# RCM-Comm_v4.net
KiCad netlist of a schematic drawn in EAGLE
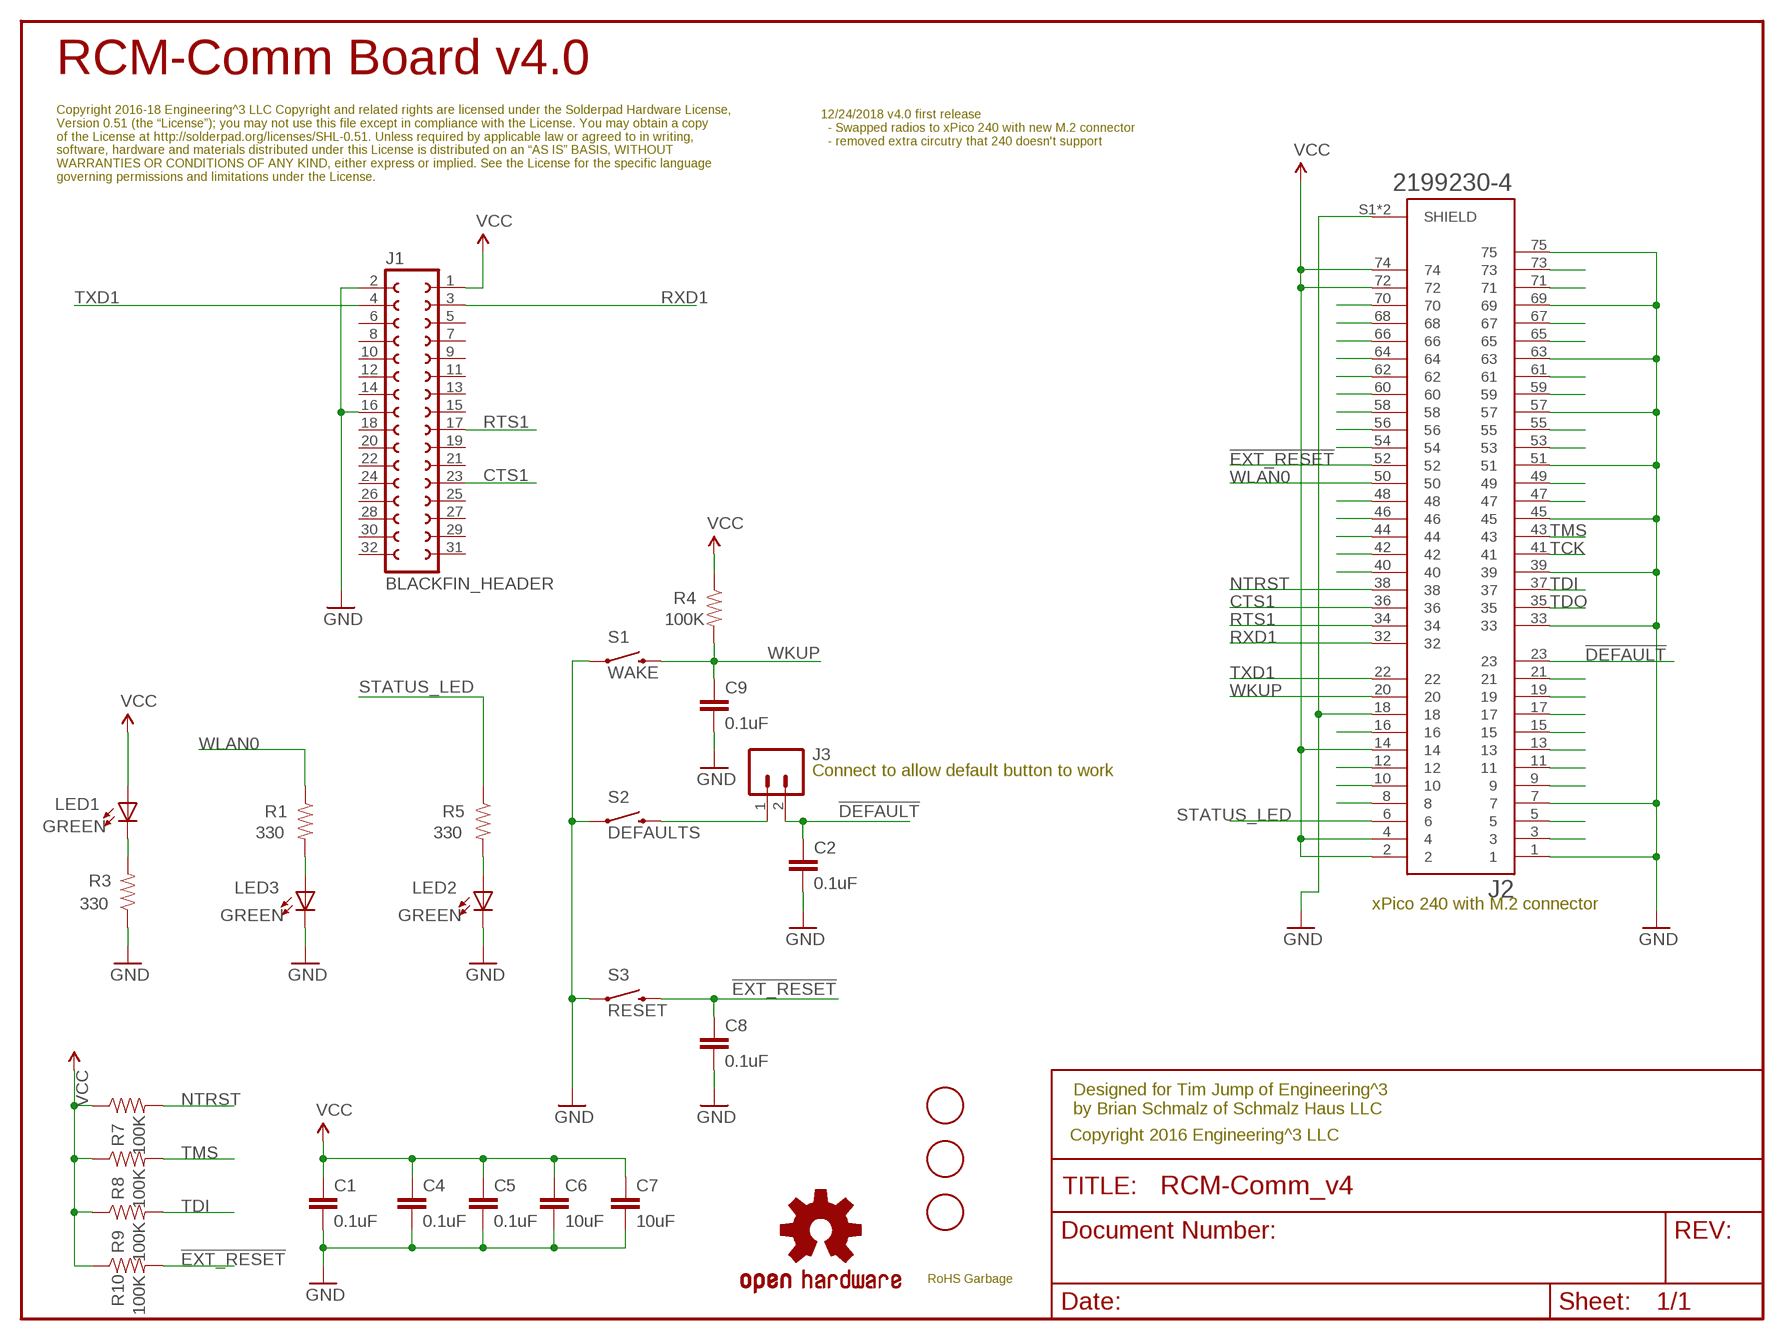
[diagram p0: schematic, sheet 1]

(export (version "E")
  (design (tool "Eeschema 10.0.6"))
  (components
    (comp (ref "C1")
      (value "0.1uF")
      (footprint "eagle-import:0603-CAP")
      (libsource (lib "eagle-import") (part "0.1UF-25V(+80/-20%)(0603)"))
    )
    (comp (ref "C2")
      (value "0.1uF")
      (footprint "eagle-import:0603-CAP")
      (libsource (lib "eagle-import") (part "0.1UF-25V(+80/-20%)(0603)"))
    )
    (comp (ref "C4")
      (value "0.1uF")
      (footprint "eagle-import:0603-CAP")
      (libsource (lib "eagle-import") (part "0.1UF-25V(+80/-20%)(0603)"))
    )
    (comp (ref "C5")
      (value "0.1uF")
      (footprint "eagle-import:0603-CAP")
      (libsource (lib "eagle-import") (part "0.1UF-25V(+80/-20%)(0603)"))
    )
    (comp (ref "C6")
      (value "10uF")
      (footprint "eagle-import:0603-CAP")
      (libsource (lib "eagle-import") (part "10UF-6.3V-20%(0603)"))
    )
    (comp (ref "C7")
      (value "10uF")
      (footprint "eagle-import:0603-CAP")
      (libsource (lib "eagle-import") (part "10UF-6.3V-20%(0603)"))
    )
    (comp (ref "C8")
      (value "0.1uF")
      (footprint "eagle-import:0603-CAP")
      (libsource (lib "eagle-import") (part "0.1UF-25V(+80/-20%)(0603)"))
    )
    (comp (ref "C9")
      (value "0.1uF")
      (footprint "eagle-import:0603-CAP")
      (libsource (lib "eagle-import") (part "0.1UF-25V(+80/-20%)(0603)"))
    )
    (comp (ref "FID1")
      (value "FIDUCIAL")
      (footprint "eagle-import:FIDUCIAL_1MM")
      (libsource (lib "eagle-import") (part "FIDUCIAL"))
    )
    (comp (ref "FID2")
      (value "FIDUCIAL")
      (footprint "eagle-import:FIDUCIAL_1MM")
      (libsource (lib "eagle-import") (part "FIDUCIAL"))
    )
    (comp (ref "FID3")
      (value "FIDUCIAL")
      (footprint "eagle-import:FIDUCIAL_1MM")
      (libsource (lib "eagle-import") (part "FIDUCIAL"))
    )
    (comp (ref "J1")
      (value "BLACKFIN_HEADER")
      (footprint "eagle-import:2X16")
      (libsource (lib "eagle-import") (part "BLACKFIN_HEADER"))
    )
    (comp (ref "J2")
      (value "2199230-4")
      (footprint "eagle-import:TE_2199230-4")
      (fields (field (name "DIGI-KEY_PART_NUMBER") "A115904CT-ND") (field (name "MF") "TE Connectivity"))
      (libsource (lib "eagle-import") (part "2199230-4"))
    )
    (comp (ref "J3")
      (value "CONN_02")
      (footprint "eagle-import:1X02")
      (libsource (lib "eagle-import") (part "CONN_02"))
    )
    (comp (ref "LED1")
      (value "GREEN")
      (footprint "eagle-import:LED-0603")
      (libsource (lib "eagle-import") (part "LED0603"))
    )
    (comp (ref "LED2")
      (value "GREEN")
      (footprint "eagle-import:LED-0603")
      (libsource (lib "eagle-import") (part "LED0603"))
    )
    (comp (ref "LED3")
      (value "GREEN")
      (footprint "eagle-import:LED-0603")
      (libsource (lib "eagle-import") (part "LED0603"))
    )
    (comp (ref "LOGO1")
      (value "OSHW-LOGOM")
      (footprint "eagle-import:OSHW-LOGO-M")
      (libsource (lib "eagle-import") (part "OSHW-LOGOM"))
    )
    (comp (ref "R1")
      (value "330")
      (footprint "eagle-import:0603-RES")
      (libsource (lib "eagle-import") (part "RESISTOR0603-RES"))
    )
    (comp (ref "R3")
      (value "330")
      (footprint "eagle-import:0603-RES")
      (libsource (lib "eagle-import") (part "RESISTOR0603-RES"))
    )
    (comp (ref "R4")
      (value "100K")
      (footprint "eagle-import:0603-RES")
      (libsource (lib "eagle-import") (part "RESISTOR0603-RES"))
    )
    (comp (ref "R5")
      (value "330")
      (footprint "eagle-import:0603-RES")
      (libsource (lib "eagle-import") (part "RESISTOR0603-RES"))
    )
    (comp (ref "R7")
      (value "100K")
      (footprint "eagle-import:0603-RES")
      (libsource (lib "eagle-import") (part "RESISTOR0603-RES"))
    )
    (comp (ref "R8")
      (value "100K")
      (footprint "eagle-import:0603-RES")
      (libsource (lib "eagle-import") (part "RESISTOR0603-RES"))
    )
    (comp (ref "R9")
      (value "100K")
      (footprint "eagle-import:0603-RES")
      (libsource (lib "eagle-import") (part "RESISTOR0603-RES"))
    )
    (comp (ref "R10")
      (value "100K")
      (footprint "eagle-import:0603-RES")
      (libsource (lib "eagle-import") (part "RESISTOR0603-RES"))
    )
    (comp (ref "S1")
      (value "WAKE")
      (footprint "eagle-import:TACTILE-SWITCH-SMD")
      (libsource (lib "eagle-import") (part "SWITCH-MOMENTARY-2SMD"))
    )
    (comp (ref "S2")
      (value "DEFAULTS")
      (footprint "eagle-import:TACTILE-SWITCH-SMD")
      (libsource (lib "eagle-import") (part "SWITCH-MOMENTARY-2SMD"))
    )
    (comp (ref "S3")
      (value "RESET")
      (footprint "eagle-import:TACTILE-SWITCH-SMD")
      (libsource (lib "eagle-import") (part "SWITCH-MOMENTARY-2SMD"))
    )
    (comp (ref "U$3")
      (value "ROHS_GARBAGE")
      (footprint "eagle-import:ROHS_GARBAGE_5MM")
      (libsource (lib "eagle-import") (part "ROHS_GARBAGE"))
    )
  )
  (nets
    (net (code "1") (name "/CTS1") (class "Default")
      (node (ref "J1") (pin "23") (pinfunction "GP6_23") (pintype "passive"))
      (node (ref "J2") (pin "36") (pinfunction "36_36") (pintype "passive"))
    )
    (net (code "2") (name "/NTRST") (class "Default")
      (node (ref "J2") (pin "38") (pinfunction "38_38") (pintype "passive"))
      (node (ref "R7") (pin "2") (pinfunction "2_2") (pintype "passive"))
    )
    (net (code "3") (name "/RTS1") (class "Default")
      (node (ref "J1") (pin "17") (pinfunction "GP0_17") (pintype "passive"))
      (node (ref "J2") (pin "34") (pinfunction "34_34") (pintype "passive"))
    )
    (net (code "4") (name "/RXD1") (class "Default")
      (node (ref "J1") (pin "3") (pinfunction "TX0_3") (pintype "passive"))
      (node (ref "J2") (pin "32") (pinfunction "32_32") (pintype "passive"))
    )
    (net (code "5") (name "/STATUS_LED") (class "Default")
      (node (ref "J2") (pin "6") (pinfunction "6_6") (pintype "passive"))
      (node (ref "R5") (pin "1") (pinfunction "1_1") (pintype "passive"))
    )
    (net (code "6") (name "/TCK") (class "Default")
      (node (ref "J2") (pin "41") (pinfunction "41_41") (pintype "passive"))
    )
    (net (code "7") (name "/TDI") (class "Default")
      (node (ref "J2") (pin "37") (pinfunction "37_37") (pintype "passive"))
      (node (ref "R9") (pin "2") (pinfunction "2_2") (pintype "passive"))
    )
    (net (code "8") (name "/TDO") (class "Default")
      (node (ref "J2") (pin "35") (pinfunction "35_35") (pintype "passive"))
    )
    (net (code "9") (name "/TMS") (class "Default")
      (node (ref "J2") (pin "43") (pinfunction "43_43") (pintype "passive"))
      (node (ref "R8") (pin "2") (pinfunction "2_2") (pintype "passive"))
    )
    (net (code "10") (name "/TXD1") (class "Default")
      (node (ref "J1") (pin "4") (pinfunction "RX0_4") (pintype "passive"))
      (node (ref "J2") (pin "22") (pinfunction "22_22") (pintype "passive"))
    )
    (net (code "11") (name "/WKUP") (class "Default")
      (node (ref "C9") (pin "1") (pinfunction "1_1") (pintype "passive"))
      (node (ref "J2") (pin "20") (pinfunction "20_20") (pintype "passive"))
      (node (ref "R4") (pin "2") (pinfunction "2_2") (pintype "passive"))
      (node (ref "S1") (pin "3") (pinfunction "2_3") (pintype "passive"))
    )
    (net (code "12") (name "/WLAN0") (class "Default")
      (node (ref "J2") (pin "50") (pinfunction "50_50") (pintype "passive"))
      (node (ref "R1") (pin "1") (pinfunction "1_1") (pintype "passive"))
    )
    (net (code "13") (name "/~{DEFAULT}") (class "Default")
      (node (ref "C2") (pin "1") (pinfunction "1_1") (pintype "passive"))
      (node (ref "J2") (pin "23") (pinfunction "23_23") (pintype "passive"))
      (node (ref "J3") (pin "2") (pinfunction "2_2") (pintype "passive"))
    )
    (net (code "14") (name "/~{EXT_RESET}") (class "Default")
      (node (ref "C8") (pin "1") (pinfunction "1_1") (pintype "passive"))
      (node (ref "J2") (pin "52") (pinfunction "52_52") (pintype "passive"))
      (node (ref "R10") (pin "2") (pinfunction "2_2") (pintype "passive"))
      (node (ref "S3") (pin "3") (pinfunction "2_3") (pintype "passive"))
    )
    (net (code "15") (name "GND") (class "Default")
      (node (ref "C1") (pin "2") (pinfunction "2_2") (pintype "passive"))
      (node (ref "C2") (pin "2") (pinfunction "2_2") (pintype "passive"))
      (node (ref "C4") (pin "2") (pinfunction "2_2") (pintype "passive"))
      (node (ref "C5") (pin "2") (pinfunction "2_2") (pintype "passive"))
      (node (ref "C6") (pin "2") (pinfunction "2_2") (pintype "passive"))
      (node (ref "C7") (pin "2") (pinfunction "2_2") (pintype "passive"))
      (node (ref "C8") (pin "2") (pinfunction "2_2") (pintype "passive"))
      (node (ref "C9") (pin "2") (pinfunction "2_2") (pintype "passive"))
      (node (ref "J1") (pin "16") (pinfunction "GND16_16") (pintype "passive"))
      (node (ref "J1") (pin "2") (pinfunction "GND_2") (pintype "passive"))
      (node (ref "J2") (pin "1") (pinfunction "1_1") (pintype "passive"))
      (node (ref "J2") (pin "18") (pinfunction "18_18") (pintype "passive"))
      (node (ref "J2") (pin "33") (pinfunction "33_33") (pintype "passive"))
      (node (ref "J2") (pin "39") (pinfunction "39_39") (pintype "passive"))
      (node (ref "J2") (pin "45") (pinfunction "45_45") (pintype "passive"))
      (node (ref "J2") (pin "51") (pinfunction "51_51") (pintype "passive"))
      (node (ref "J2") (pin "57") (pinfunction "57_57") (pintype "passive"))
      (node (ref "J2") (pin "63") (pinfunction "63_63") (pintype "passive"))
      (node (ref "J2") (pin "69") (pinfunction "69_69") (pintype "passive"))
      (node (ref "J2") (pin "7") (pinfunction "7_7") (pintype "passive"))
      (node (ref "J2") (pin "75") (pinfunction "75_75") (pintype "passive"))
      (node (ref "J2") (pin "S1") (pinfunction "SHIELD_S1") (pintype "passive"))
      (node (ref "J2") (pin "S2") (pinfunction "SHIELD_S2") (pintype "passive"))
      (node (ref "LED2") (pin "C") (pinfunction "C_C") (pintype "passive"))
      (node (ref "LED3") (pin "C") (pinfunction "C_C") (pintype "passive"))
      (node (ref "R3") (pin "1") (pinfunction "1_1") (pintype "passive"))
      (node (ref "S1") (pin "1") (pinfunction "1_1") (pintype "passive"))
      (node (ref "S2") (pin "1") (pinfunction "1_1") (pintype "passive"))
      (node (ref "S3") (pin "1") (pinfunction "1_1") (pintype "passive"))
    )
    (net (code "16") (name "Net-(LED1-PadC)") (class "Default")
      (node (ref "LED1") (pin "C") (pinfunction "C_C") (pintype "passive"))
      (node (ref "R3") (pin "2") (pinfunction "2_2") (pintype "passive"))
    )
    (net (code "17") (name "Net-(LED2-PadA)") (class "Default")
      (node (ref "LED2") (pin "A") (pinfunction "A_A") (pintype "passive"))
      (node (ref "R5") (pin "2") (pinfunction "2_2") (pintype "passive"))
    )
    (net (code "18") (name "Net-(LED3-PadA)") (class "Default")
      (node (ref "LED3") (pin "A") (pinfunction "A_A") (pintype "passive"))
      (node (ref "R1") (pin "2") (pinfunction "2_2") (pintype "passive"))
    )
    (net (code "19") (name "Net-(S2-2)") (class "Default")
      (node (ref "J3") (pin "1") (pinfunction "1_1") (pintype "passive"))
      (node (ref "S2") (pin "3") (pinfunction "2_3") (pintype "passive"))
    )
    (net (code "20") (name "VCC") (class "Default")
      (node (ref "C1") (pin "1") (pinfunction "1_1") (pintype "passive"))
      (node (ref "C4") (pin "1") (pinfunction "1_1") (pintype "passive"))
      (node (ref "C5") (pin "1") (pinfunction "1_1") (pintype "passive"))
      (node (ref "C6") (pin "1") (pinfunction "1_1") (pintype "passive"))
      (node (ref "C7") (pin "1") (pinfunction "1_1") (pintype "passive"))
      (node (ref "J1") (pin "1") (pinfunction "3.3V_1") (pintype "passive"))
      (node (ref "J2") (pin "14") (pinfunction "14_14") (pintype "passive"))
      (node (ref "J2") (pin "2") (pinfunction "2_2") (pintype "passive"))
      (node (ref "J2") (pin "4") (pinfunction "4_4") (pintype "passive"))
      (node (ref "J2") (pin "72") (pinfunction "72_72") (pintype "passive"))
      (node (ref "J2") (pin "74") (pinfunction "74_74") (pintype "passive"))
      (node (ref "LED1") (pin "A") (pinfunction "A_A") (pintype "passive"))
      (node (ref "R10") (pin "1") (pinfunction "1_1") (pintype "passive"))
      (node (ref "R4") (pin "1") (pinfunction "1_1") (pintype "passive"))
      (node (ref "R7") (pin "1") (pinfunction "1_1") (pintype "passive"))
      (node (ref "R8") (pin "1") (pinfunction "1_1") (pintype "passive"))
      (node (ref "R9") (pin "1") (pinfunction "1_1") (pintype "passive"))
    )
    (net (code "21") (name "unconnected-(J1-GP1-Pad18)") (class "Default")
      (node (ref "J1") (pin "18") (pinfunction "GP1_18") (pintype "passive"))
    )
    (net (code "22") (name "unconnected-(J1-GP2-Pad19)") (class "Default")
      (node (ref "J1") (pin "19") (pinfunction "GP2_19") (pintype "passive"))
    )
    (net (code "23") (name "unconnected-(J1-GP3-Pad20)") (class "Default")
      (node (ref "J1") (pin "20") (pinfunction "GP3_20") (pintype "passive"))
    )
    (net (code "24") (name "unconnected-(J1-GP4-Pad21)") (class "Default")
      (node (ref "J1") (pin "21") (pinfunction "GP4_21") (pintype "passive"))
    )
    (net (code "25") (name "unconnected-(J1-GP5-Pad22)") (class "Default")
      (node (ref "J1") (pin "22") (pinfunction "GP5_22") (pintype "passive"))
    )
    (net (code "26") (name "unconnected-(J1-GP7-Pad24)") (class "Default")
      (node (ref "J1") (pin "24") (pinfunction "GP7_24") (pintype "passive"))
    )
    (net (code "27") (name "unconnected-(J1-GP8-Pad25)") (class "Default")
      (node (ref "J1") (pin "25") (pinfunction "GP8_25") (pintype "passive"))
    )
    (net (code "28") (name "unconnected-(J1-GP9-Pad26)") (class "Default")
      (node (ref "J1") (pin "26") (pinfunction "GP9_26") (pintype "passive"))
    )
    (net (code "29") (name "unconnected-(J1-GPA-Pad27)") (class "Default")
      (node (ref "J1") (pin "27") (pinfunction "GPA_27") (pintype "passive"))
    )
    (net (code "30") (name "unconnected-(J1-GPB-Pad28)") (class "Default")
      (node (ref "J1") (pin "28") (pinfunction "GPB_28") (pintype "passive"))
    )
    (net (code "31") (name "unconnected-(J1-GPC-Pad29)") (class "Default")
      (node (ref "J1") (pin "29") (pinfunction "GPC_29") (pintype "passive"))
    )
    (net (code "32") (name "unconnected-(J1-GPD-Pad30)") (class "Default")
      (node (ref "J1") (pin "30") (pinfunction "GPD_30") (pintype "passive"))
    )
    (net (code "33") (name "unconnected-(J1-GPE-Pad31)") (class "Default")
      (node (ref "J1") (pin "31") (pinfunction "GPE_31") (pintype "passive"))
    )
    (net (code "34") (name "unconnected-(J1-GPF-Pad32)") (class "Default")
      (node (ref "J1") (pin "32") (pinfunction "GPF_32") (pintype "passive"))
    )
    (net (code "35") (name "unconnected-(J1-I2C_SDA-Pad15)") (class "Default")
      (node (ref "J1") (pin "15") (pinfunction "I2C_SDA_15") (pintype "passive"))
    )
    (net (code "36") (name "unconnected-(J1-RX1-Pad6)") (class "Default")
      (node (ref "J1") (pin "6") (pinfunction "RX1_6") (pintype "passive"))
    )
    (net (code "37") (name "unconnected-(J1-SPI_MISO-Pad10)") (class "Default")
      (node (ref "J1") (pin "10") (pinfunction "SPI_MISO_10") (pintype "passive"))
    )
    (net (code "38") (name "unconnected-(J1-SPI_MOSI-Pad9)") (class "Default")
      (node (ref "J1") (pin "9") (pinfunction "SPI_MOSI_9") (pintype "passive"))
    )
    (net (code "39") (name "unconnected-(J1-SPI_SCK-Pad11)") (class "Default")
      (node (ref "J1") (pin "11") (pinfunction "SPI_SCK_11") (pintype "passive"))
    )
    (net (code "40") (name "unconnected-(J1-SPI_SCL-Pad14)") (class "Default")
      (node (ref "J1") (pin "14") (pinfunction "SPI_SCL_14") (pintype "passive"))
    )
    (net (code "41") (name "unconnected-(J1-SPI_SEL-Pad12)") (class "Default")
      (node (ref "J1") (pin "12") (pinfunction "SPI_SEL_12") (pintype "passive"))
    )
    (net (code "42") (name "unconnected-(J1-SPI_SEL2-Pad13)") (class "Default")
      (node (ref "J1") (pin "13") (pinfunction "SPI_SEL2_13") (pintype "passive"))
    )
    (net (code "43") (name "unconnected-(J1-TMR2-Pad7)") (class "Default")
      (node (ref "J1") (pin "7") (pinfunction "TMR2_7") (pintype "passive"))
    )
    (net (code "44") (name "unconnected-(J1-TMR3-Pad8)") (class "Default")
      (node (ref "J1") (pin "8") (pinfunction "TMR3_8") (pintype "passive"))
    )
    (net (code "45") (name "unconnected-(J1-TX1-Pad5)") (class "Default")
      (node (ref "J1") (pin "5") (pinfunction "TX1_5") (pintype "passive"))
    )
    (net (code "46") (name "unconnected-(J2-Pad3)") (class "Default")
      (node (ref "J2") (pin "3") (pinfunction "3_3") (pintype "passive"))
    )
    (net (code "47") (name "unconnected-(J2-Pad5)") (class "Default")
      (node (ref "J2") (pin "5") (pinfunction "5_5") (pintype "passive"))
    )
    (net (code "48") (name "unconnected-(J2-Pad8)") (class "Default")
      (node (ref "J2") (pin "8") (pinfunction "8_8") (pintype "passive"))
    )
    (net (code "49") (name "unconnected-(J2-Pad9)") (class "Default")
      (node (ref "J2") (pin "9") (pinfunction "9_9") (pintype "passive"))
    )
    (net (code "50") (name "unconnected-(J2-Pad10)") (class "Default")
      (node (ref "J2") (pin "10") (pinfunction "10_10") (pintype "passive"))
    )
    (net (code "51") (name "unconnected-(J2-Pad11)") (class "Default")
      (node (ref "J2") (pin "11") (pinfunction "11_11") (pintype "passive"))
    )
    (net (code "52") (name "unconnected-(J2-Pad12)") (class "Default")
      (node (ref "J2") (pin "12") (pinfunction "12_12") (pintype "passive"))
    )
    (net (code "53") (name "unconnected-(J2-Pad13)") (class "Default")
      (node (ref "J2") (pin "13") (pinfunction "13_13") (pintype "passive"))
    )
    (net (code "54") (name "unconnected-(J2-Pad15)") (class "Default")
      (node (ref "J2") (pin "15") (pinfunction "15_15") (pintype "passive"))
    )
    (net (code "55") (name "unconnected-(J2-Pad16)") (class "Default")
      (node (ref "J2") (pin "16") (pinfunction "16_16") (pintype "passive"))
    )
    (net (code "56") (name "unconnected-(J2-Pad17)") (class "Default")
      (node (ref "J2") (pin "17") (pinfunction "17_17") (pintype "passive"))
    )
    (net (code "57") (name "unconnected-(J2-Pad19)") (class "Default")
      (node (ref "J2") (pin "19") (pinfunction "19_19") (pintype "passive"))
    )
    (net (code "58") (name "unconnected-(J2-Pad21)") (class "Default")
      (node (ref "J2") (pin "21") (pinfunction "21_21") (pintype "passive"))
    )
    (net (code "59") (name "unconnected-(J2-Pad40)") (class "Default")
      (node (ref "J2") (pin "40") (pinfunction "40_40") (pintype "passive"))
    )
    (net (code "60") (name "unconnected-(J2-Pad42)") (class "Default")
      (node (ref "J2") (pin "42") (pinfunction "42_42") (pintype "passive"))
    )
    (net (code "61") (name "unconnected-(J2-Pad44)") (class "Default")
      (node (ref "J2") (pin "44") (pinfunction "44_44") (pintype "passive"))
    )
    (net (code "62") (name "unconnected-(J2-Pad46)") (class "Default")
      (node (ref "J2") (pin "46") (pinfunction "46_46") (pintype "passive"))
    )
    (net (code "63") (name "unconnected-(J2-Pad47)") (class "Default")
      (node (ref "J2") (pin "47") (pinfunction "47_47") (pintype "passive"))
    )
    (net (code "64") (name "unconnected-(J2-Pad48)") (class "Default")
      (node (ref "J2") (pin "48") (pinfunction "48_48") (pintype "passive"))
    )
    (net (code "65") (name "unconnected-(J2-Pad49)") (class "Default")
      (node (ref "J2") (pin "49") (pinfunction "49_49") (pintype "passive"))
    )
    (net (code "66") (name "unconnected-(J2-Pad53)") (class "Default")
      (node (ref "J2") (pin "53") (pinfunction "53_53") (pintype "passive"))
    )
    (net (code "67") (name "unconnected-(J2-Pad54)") (class "Default")
      (node (ref "J2") (pin "54") (pinfunction "54_54") (pintype "passive"))
    )
    (net (code "68") (name "unconnected-(J2-Pad55)") (class "Default")
      (node (ref "J2") (pin "55") (pinfunction "55_55") (pintype "passive"))
    )
    (net (code "69") (name "unconnected-(J2-Pad56)") (class "Default")
      (node (ref "J2") (pin "56") (pinfunction "56_56") (pintype "passive"))
    )
    (net (code "70") (name "unconnected-(J2-Pad58)") (class "Default")
      (node (ref "J2") (pin "58") (pinfunction "58_58") (pintype "passive"))
    )
    (net (code "71") (name "unconnected-(J2-Pad59)") (class "Default")
      (node (ref "J2") (pin "59") (pinfunction "59_59") (pintype "passive"))
    )
    (net (code "72") (name "unconnected-(J2-Pad60)") (class "Default")
      (node (ref "J2") (pin "60") (pinfunction "60_60") (pintype "passive"))
    )
    (net (code "73") (name "unconnected-(J2-Pad61)") (class "Default")
      (node (ref "J2") (pin "61") (pinfunction "61_61") (pintype "passive"))
    )
    (net (code "74") (name "unconnected-(J2-Pad62)") (class "Default")
      (node (ref "J2") (pin "62") (pinfunction "62_62") (pintype "passive"))
    )
    (net (code "75") (name "unconnected-(J2-Pad64)") (class "Default")
      (node (ref "J2") (pin "64") (pinfunction "64_64") (pintype "passive"))
    )
    (net (code "76") (name "unconnected-(J2-Pad65)") (class "Default")
      (node (ref "J2") (pin "65") (pinfunction "65_65") (pintype "passive"))
    )
    (net (code "77") (name "unconnected-(J2-Pad66)") (class "Default")
      (node (ref "J2") (pin "66") (pinfunction "66_66") (pintype "passive"))
    )
    (net (code "78") (name "unconnected-(J2-Pad67)") (class "Default")
      (node (ref "J2") (pin "67") (pinfunction "67_67") (pintype "passive"))
    )
    (net (code "79") (name "unconnected-(J2-Pad68)") (class "Default")
      (node (ref "J2") (pin "68") (pinfunction "68_68") (pintype "passive"))
    )
    (net (code "80") (name "unconnected-(J2-Pad70)") (class "Default")
      (node (ref "J2") (pin "70") (pinfunction "70_70") (pintype "passive"))
    )
    (net (code "81") (name "unconnected-(J2-Pad71)") (class "Default")
      (node (ref "J2") (pin "71") (pinfunction "71_71") (pintype "passive"))
    )
    (net (code "82") (name "unconnected-(J2-Pad73)") (class "Default")
      (node (ref "J2") (pin "73") (pinfunction "73_73") (pintype "passive"))
    )
  )
)
